# ptFlex.net
KiCad netlist of a schematic drawn in EAGLE
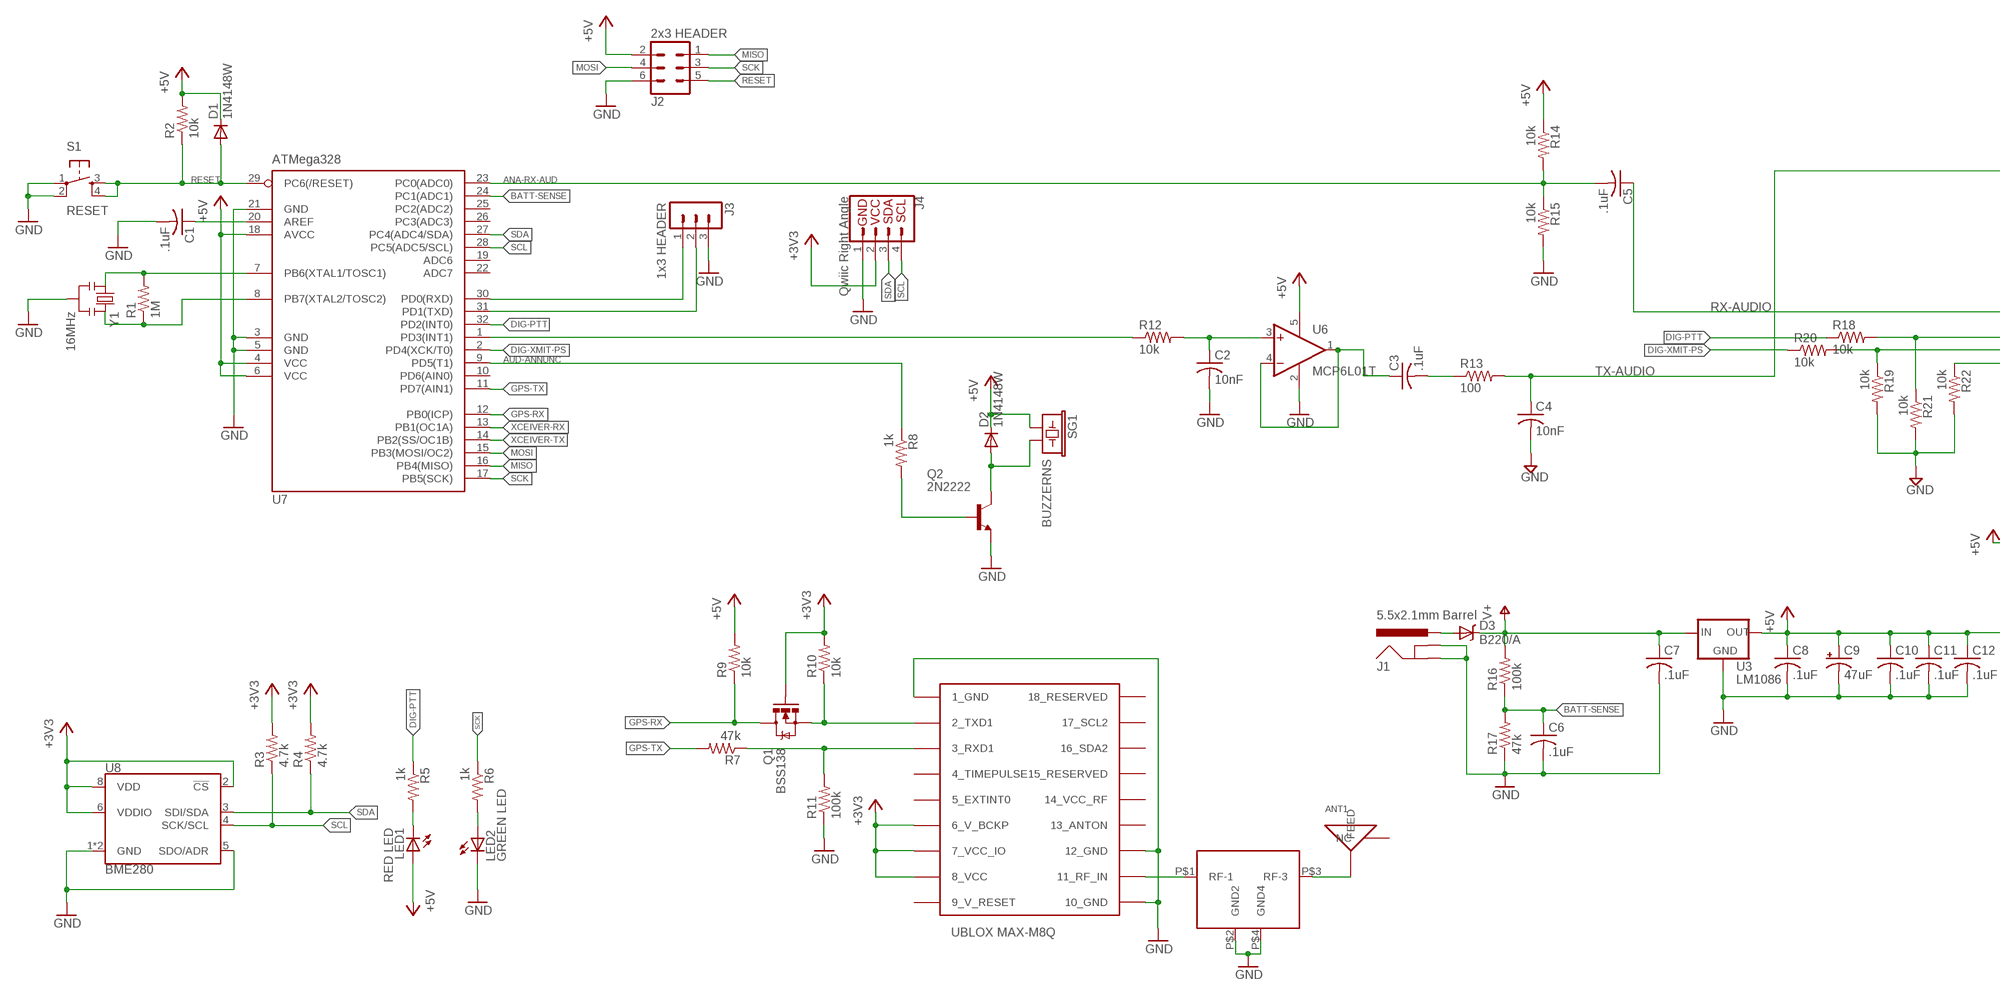
[diagram p0: schematic, sheet 1, part 1 of 2]
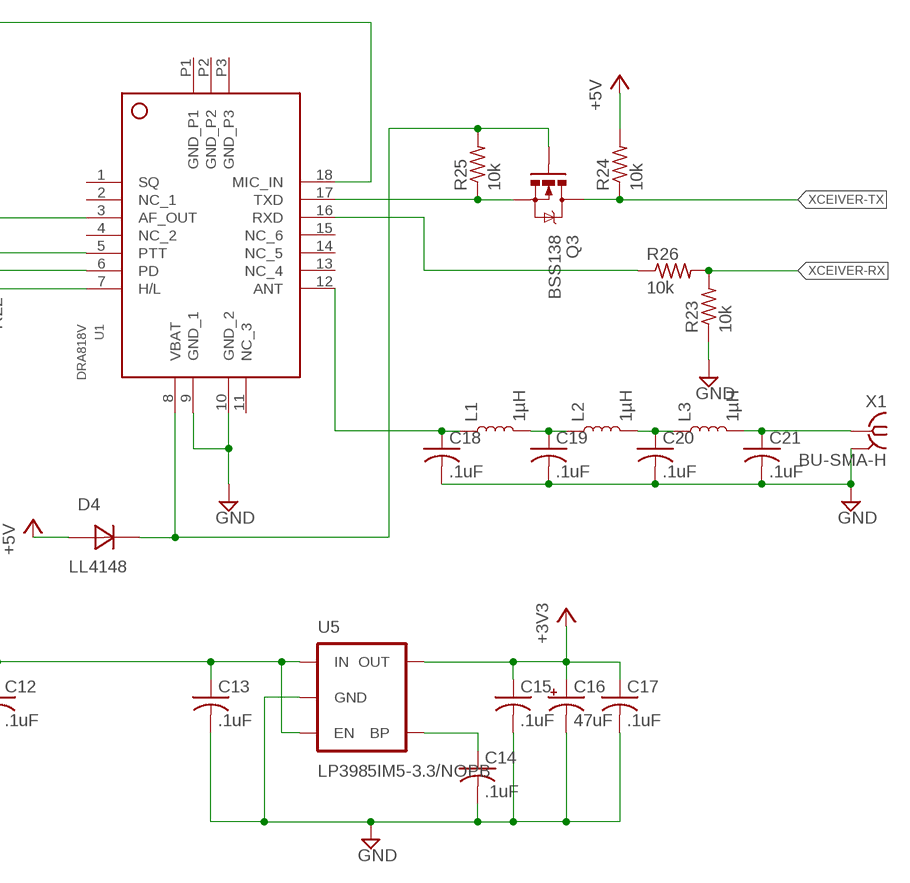
[diagram p1: schematic, sheet 1, part 2 of 2]

(export (version "E")
  (design (tool "Eeschema 10.0.6"))
  (components
    (comp (ref "ANT1")
      (value "GPS ANTENNA")
      (footprint "eagle-import:1575AT43A40")
      (libsource (lib "eagle-import") (part "GPS_ANT_SMDBAR"))
    )
    (comp (ref "C1")
      (value ".1uF")
      (footprint "eagle-import:C0805")
      (libsource (lib "eagle-import") (part "C-USC0805"))
    )
    (comp (ref "C2")
      (value "10nF")
      (footprint "eagle-import:C0805")
      (libsource (lib "eagle-import") (part "C-USC0805"))
    )
    (comp (ref "C3")
      (value ".1uF")
      (footprint "eagle-import:C0805")
      (libsource (lib "eagle-import") (part "C-USC0805"))
    )
    (comp (ref "C4")
      (value "10nF")
      (footprint "eagle-import:C0805")
      (libsource (lib "eagle-import") (part "C-USC0805"))
    )
    (comp (ref "C5")
      (value ".1uF")
      (footprint "eagle-import:C0805")
      (libsource (lib "eagle-import") (part "C-USC0805"))
    )
    (comp (ref "C6")
      (value ".1uF")
      (footprint "eagle-import:C0805")
      (libsource (lib "eagle-import") (part "C-USC0805"))
    )
    (comp (ref "C7")
      (value ".1uF")
      (footprint "eagle-import:C0805")
      (libsource (lib "eagle-import") (part "C-USC0805"))
    )
    (comp (ref "C8")
      (value ".1uF")
      (footprint "eagle-import:C0805")
      (libsource (lib "eagle-import") (part "C-USC0805"))
    )
    (comp (ref "C9")
      (value "47uF")
      (footprint "eagle-import:153CLV-0605")
      (libsource (lib "eagle-import") (part "CPOL-US153CLV-0605"))
    )
    (comp (ref "C10")
      (value ".1uF")
      (footprint "eagle-import:C0805")
      (libsource (lib "eagle-import") (part "C-USC0805"))
    )
    (comp (ref "C11")
      (value ".1uF")
      (footprint "eagle-import:C0805")
      (libsource (lib "eagle-import") (part "C-USC0805"))
    )
    (comp (ref "C12")
      (value ".1uF")
      (footprint "eagle-import:C0805")
      (libsource (lib "eagle-import") (part "C-USC0805"))
    )
    (comp (ref "C13")
      (value ".1uF")
      (footprint "eagle-import:C0805")
      (libsource (lib "eagle-import") (part "C-USC0805"))
    )
    (comp (ref "C14")
      (value ".1uF")
      (footprint "eagle-import:C0805")
      (libsource (lib "eagle-import") (part "C-USC0805"))
    )
    (comp (ref "C15")
      (value ".1uF")
      (footprint "eagle-import:C0805")
      (libsource (lib "eagle-import") (part "C-USC0805"))
    )
    (comp (ref "C16")
      (value "47uF")
      (footprint "eagle-import:153CLV-0605")
      (libsource (lib "eagle-import") (part "CPOL-US153CLV-0605"))
    )
    (comp (ref "C17")
      (value ".1uF")
      (footprint "eagle-import:C0805")
      (libsource (lib "eagle-import") (part "C-USC0805"))
    )
    (comp (ref "C18")
      (value ".1uF")
      (footprint "eagle-import:C0805")
      (libsource (lib "eagle-import") (part "C-USC0805"))
    )
    (comp (ref "C19")
      (value ".1uF")
      (footprint "eagle-import:C0805")
      (libsource (lib "eagle-import") (part "C-USC0805"))
    )
    (comp (ref "C20")
      (value ".1uF")
      (footprint "eagle-import:C0805")
      (libsource (lib "eagle-import") (part "C-USC0805"))
    )
    (comp (ref "C21")
      (value ".1uF")
      (footprint "eagle-import:C0805")
      (libsource (lib "eagle-import") (part "C-USC0805"))
    )
    (comp (ref "D1")
      (value "1N4148W")
      (footprint "eagle-import:SOD123")
      (libsource (lib "eagle-import") (part "DIODE-SOD123"))
    )
    (comp (ref "D2")
      (value "1N4148W")
      (footprint "eagle-import:SOD123")
      (libsource (lib "eagle-import") (part "DIODE-SOD123"))
    )
    (comp (ref "D3")
      (value "B220/A")
      (footprint "eagle-import:SMA-DIODE")
      (libsource (lib "eagle-import") (part "B340A"))
    )
    (comp (ref "D4")
      (value "LL4148")
      (footprint "eagle-import:SOD-80")
      (libsource (lib "eagle-import") (part "LL4148"))
    )
    (comp (ref "F1")
      (value "MURATA-GPS-FILTER")
      (footprint "eagle-import:MURATA-GPS-FILTER")
      (libsource (lib "eagle-import") (part "MURATA-GPS-FILTER"))
    )
    (comp (ref "J1")
      (value "5.5x2.1mm Barrel")
      (footprint "eagle-import:POWER_JACK_SMD")
      (libsource (lib "eagle-import") (part "POWER_JACKSMD"))
    )
    (comp (ref "J2")
      (value "2x3 HEADER")
      (footprint "eagle-import:MA03-2")
      (libsource (lib "eagle-import") (part "MA03-2"))
    )
    (comp (ref "J3")
      (value "1x3 HEADER")
      (footprint "eagle-import:MA03-1")
      (libsource (lib "eagle-import") (part "MA03-1"))
    )
    (comp (ref "J4")
      (value "Qwiic Right Angle")
      (footprint "eagle-import:1X04_1MM_RA")
      (libsource (lib "eagle-import") (part "I2C_STANDARDQWIIC"))
    )
    (comp (ref "L1")
      (value "1µH")
      (footprint "eagle-import:L0805")
      (libsource (lib "eagle-import") (part "INDUCTOR"))
    )
    (comp (ref "L2")
      (value "1µH")
      (footprint "eagle-import:L0805")
      (libsource (lib "eagle-import") (part "INDUCTOR"))
    )
    (comp (ref "L3")
      (value "1µH")
      (footprint "eagle-import:L0805")
      (libsource (lib "eagle-import") (part "INDUCTOR"))
    )
    (comp (ref "LED1")
      (value "RED LED")
      (footprint "eagle-import:CHIPLED_1206")
      (libsource (lib "eagle-import") (part "LEDCHIPLED_1206"))
    )
    (comp (ref "LED2")
      (value "GREEN LED")
      (footprint "eagle-import:CHIPLED_1206")
      (libsource (lib "eagle-import") (part "LEDCHIPLED_1206"))
    )
    (comp (ref "Q1")
      (value "BSS138")
      (footprint "eagle-import:SOT23")
      (libsource (lib "eagle-import") (part "MOSFET-NCHANNELBSS138"))
    )
    (comp (ref "Q2")
      (value "2N2222")
      (footprint "eagle-import:SOT23-BEC")
      (libsource (lib "eagle-import") (part "BC817SMD-16LT1"))
    )
    (comp (ref "Q3")
      (value "BSS138")
      (footprint "eagle-import:SOT23")
      (libsource (lib "eagle-import") (part "MOSFET-NCHANNELBSS138"))
    )
    (comp (ref "R1")
      (value "1M")
      (footprint "eagle-import:R0805")
      (libsource (lib "eagle-import") (part "R-US_R0805"))
    )
    (comp (ref "R2")
      (value "10k")
      (footprint "eagle-import:R0805")
      (libsource (lib "eagle-import") (part "R-US_R0805"))
    )
    (comp (ref "R3")
      (value "4.7k")
      (footprint "eagle-import:R0805")
      (libsource (lib "eagle-import") (part "R-US_R0805"))
    )
    (comp (ref "R4")
      (value "4.7k")
      (footprint "eagle-import:R0805")
      (libsource (lib "eagle-import") (part "R-US_R0805"))
    )
    (comp (ref "R5")
      (value "1k")
      (footprint "eagle-import:R0805")
      (libsource (lib "eagle-import") (part "R-US_R0805"))
    )
    (comp (ref "R6")
      (value "1k")
      (footprint "eagle-import:R0805")
      (libsource (lib "eagle-import") (part "R-US_R0805"))
    )
    (comp (ref "R7")
      (value "47k")
      (footprint "eagle-import:R0805")
      (libsource (lib "eagle-import") (part "R-US_R0805"))
    )
    (comp (ref "R8")
      (value "1k")
      (footprint "eagle-import:R0805")
      (libsource (lib "eagle-import") (part "R-US_R0805"))
    )
    (comp (ref "R9")
      (value "10k")
      (footprint "eagle-import:R0805")
      (libsource (lib "eagle-import") (part "R-US_R0805"))
    )
    (comp (ref "R10")
      (value "10k")
      (footprint "eagle-import:R0805")
      (libsource (lib "eagle-import") (part "R-US_R0805"))
    )
    (comp (ref "R11")
      (value "100k")
      (footprint "eagle-import:R0805")
      (libsource (lib "eagle-import") (part "R-US_R0805"))
    )
    (comp (ref "R12")
      (value "10k")
      (footprint "eagle-import:R0805")
      (libsource (lib "eagle-import") (part "R-US_R0805"))
    )
    (comp (ref "R13")
      (value "100")
      (footprint "eagle-import:R0805")
      (libsource (lib "eagle-import") (part "R-US_R0805"))
    )
    (comp (ref "R14")
      (value "10k")
      (footprint "eagle-import:R0805")
      (libsource (lib "eagle-import") (part "R-US_R0805"))
    )
    (comp (ref "R15")
      (value "10k")
      (footprint "eagle-import:R0805")
      (libsource (lib "eagle-import") (part "R-US_R0805"))
    )
    (comp (ref "R16")
      (value "100k")
      (footprint "eagle-import:R0805")
      (libsource (lib "eagle-import") (part "R-US_R0805"))
    )
    (comp (ref "R17")
      (value "47k")
      (footprint "eagle-import:R0805")
      (libsource (lib "eagle-import") (part "R-US_R0805"))
    )
    (comp (ref "R18")
      (value "10k")
      (footprint "eagle-import:R0805")
      (libsource (lib "eagle-import") (part "R-US_R0805"))
    )
    (comp (ref "R19")
      (value "10k")
      (footprint "eagle-import:R0805")
      (libsource (lib "eagle-import") (part "R-US_R0805"))
    )
    (comp (ref "R20")
      (value "10k")
      (footprint "eagle-import:R0805")
      (libsource (lib "eagle-import") (part "R-US_R0805"))
    )
    (comp (ref "R21")
      (value "10k")
      (footprint "eagle-import:R0805")
      (libsource (lib "eagle-import") (part "R-US_R0805"))
    )
    (comp (ref "R22")
      (value "10k")
      (footprint "eagle-import:R0805")
      (libsource (lib "eagle-import") (part "R-US_R0805"))
    )
    (comp (ref "R23")
      (value "10k")
      (footprint "eagle-import:R0805")
      (libsource (lib "eagle-import") (part "R-US_R0805"))
    )
    (comp (ref "R24")
      (value "10k")
      (footprint "eagle-import:R0805")
      (libsource (lib "eagle-import") (part "R-US_R0805"))
    )
    (comp (ref "R25")
      (value "10k")
      (footprint "eagle-import:R0805")
      (libsource (lib "eagle-import") (part "R-US_R0805"))
    )
    (comp (ref "R26")
      (value "10k")
      (footprint "eagle-import:R0805")
      (libsource (lib "eagle-import") (part "R-US_R0805"))
    )
    (comp (ref "S1")
      (value "RESET")
      (footprint "eagle-import:TACTILE_SWITCH_SMD")
      (libsource (lib "eagle-import") (part "TAC_SWITCHSMD"))
    )
    (comp (ref "SG1")
      (value "BUZZERNS")
      (footprint "eagle-import:BUZZER-12MM-NS")
      (libsource (lib "eagle-import") (part "BUZZERNS"))
    )
    (comp (ref "U1")
      (value "DRA818V")
      (footprint "eagle-import:SMD_DRA818")
      (libsource (lib "eagle-import") (part "DRA818V"))
    )
    (comp (ref "U2")
      (value "UBLOX_MAX")
      (footprint "eagle-import:UBLOX_MAX")
      (fields (field (name "ALT-PART") "UBLOX MAX-M8Q"))
      (libsource (lib "eagle-import") (part "UBLOX_MAX"))
    )
    (comp (ref "U3")
      (value "LM1086")
      (footprint "eagle-import:TO263")
      (libsource (lib "eagle-import") (part "LM1086TO263"))
    )
    (comp (ref "U5")
      (value "LP3985IM5-3.3/NOPB")
      (footprint "eagle-import:SOT23-5")
      (libsource (lib "eagle-import") (part "V_REG_LDOSMD"))
    )
    (comp (ref "U6")
      (value "MCP6L01T")
      (footprint "eagle-import:SOT23-5")
      (libsource (lib "eagle-import") (part "OPA725DBV"))
    )
    (comp (ref "U7")
      (value "ATMega328")
      (footprint "eagle-import:TQFP32-08")
      (fields (field (name "MPN") "ATMEGA8-16AU"))
      (libsource (lib "eagle-import") (part "MEGA8-AI"))
    )
    (comp (ref "U8")
      (value "BME280")
      (footprint "eagle-import:LGA-8-2.5X2.5")
      (libsource (lib "eagle-import") (part "BME280"))
    )
    (comp (ref "X1")
      (value "BU-SMA-H")
      (footprint "eagle-import:BU-SMA-H")
      (libsource (lib "eagle-import") (part "BU-SMA-H"))
    )
    (comp (ref "Y1")
      (value "16MHz")
      (footprint "eagle-import:RESONATOR-SMD")
      (libsource (lib "eagle-import") (part "RESONATOR16MHZ"))
    )
  )
  (nets
    (net (code "1") (name "+3V3") (class "Default")
      (node (ref "C15") (pin "1") (pinfunction "1_1") (pintype "passive"))
      (node (ref "C16") (pin "+") (pinfunction "+_+") (pintype "passive"))
      (node (ref "C17") (pin "1") (pinfunction "1_1") (pintype "passive"))
      (node (ref "J4") (pin "2") (pinfunction "2_2") (pintype "power_in"))
      (node (ref "Q1") (pin "1") (pinfunction "G_1") (pintype "passive"))
      (node (ref "R10") (pin "2") (pinfunction "2_2") (pintype "passive"))
      (node (ref "R3") (pin "2") (pinfunction "2_2") (pintype "passive"))
      (node (ref "R4") (pin "2") (pinfunction "2_2") (pintype "passive"))
      (node (ref "U2") (pin "6_V_BCKP") (pinfunction "6_V_BCKP_6_V_BCKP") (pintype "bidirectional"))
      (node (ref "U2") (pin "7_VCC_IO") (pinfunction "7_VCC_IO_7_VCC_IO") (pintype "power_in"))
      (node (ref "U2") (pin "8_VCC") (pinfunction "8_VCC_8_VCC") (pintype "power_in"))
      (node (ref "U5") (pin "5") (pinfunction "OUT_5") (pintype "passive"))
      (node (ref "U8") (pin "2") (pinfunction "~{CS}_2") (pintype "bidirectional"))
      (node (ref "U8") (pin "6") (pinfunction "VDDIO_6") (pintype "bidirectional"))
      (node (ref "U8") (pin "8") (pinfunction "VDD_8") (pintype "bidirectional"))
    )
    (net (code "2") (name "+5V") (class "Default")
      (node (ref "C10") (pin "1") (pinfunction "1_1") (pintype "passive"))
      (node (ref "C11") (pin "1") (pinfunction "1_1") (pintype "passive"))
      (node (ref "C12") (pin "1") (pinfunction "1_1") (pintype "passive"))
      (node (ref "C13") (pin "1") (pinfunction "1_1") (pintype "passive"))
      (node (ref "C8") (pin "1") (pinfunction "1_1") (pintype "passive"))
      (node (ref "C9") (pin "+") (pinfunction "+_+") (pintype "passive"))
      (node (ref "D1") (pin "C") (pinfunction "C_C") (pintype "passive"))
      (node (ref "D2") (pin "C") (pinfunction "C_C") (pintype "passive"))
      (node (ref "D4") (pin "ANODE") (pinfunction "ANODE_ANODE") (pintype "passive"))
      (node (ref "J2") (pin "2") (pinfunction "2_2") (pintype "passive"))
      (node (ref "LED1") (pin "A") (pinfunction "A_A") (pintype "passive"))
      (node (ref "R14") (pin "1") (pinfunction "1_1") (pintype "passive"))
      (node (ref "R2") (pin "2") (pinfunction "2_2") (pintype "passive"))
      (node (ref "R24") (pin "2") (pinfunction "2_2") (pintype "passive"))
      (node (ref "R9") (pin "2") (pinfunction "2_2") (pintype "passive"))
      (node (ref "SG1") (pin "+") (pinfunction "1_+") (pintype "passive"))
      (node (ref "U3") (pin "2") (pinfunction "OUT_2") (pintype "passive"))
      (node (ref "U5") (pin "1") (pinfunction "IN_1") (pintype "input"))
      (node (ref "U5") (pin "3") (pinfunction "EN_3") (pintype "input"))
      (node (ref "U6") (pin "5") (pinfunction "V+_5") (pintype "power_in"))
      (node (ref "U7") (pin "18") (pinfunction "AVCC_18") (pintype "power_in"))
      (node (ref "U7") (pin "4") (pinfunction "VCC_4") (pintype "power_in"))
      (node (ref "U7") (pin "6") (pinfunction "VCC_6") (pintype "power_in"))
    )
    (net (code "3") (name "/9_V_RESET") (class "Default")
      (node (ref "U2") (pin "9_V_RESET") (pinfunction "9_V_RESET_9_V_RESET") (pintype "power_in"))
    )
    (net (code "4") (name "/ANA-RX-AUD") (class "Default")
      (node (ref "C5") (pin "2") (pinfunction "2_2") (pintype "passive"))
      (node (ref "R14") (pin "2") (pinfunction "2_2") (pintype "passive"))
      (node (ref "R15") (pin "1") (pinfunction "1_1") (pintype "passive"))
      (node (ref "U7") (pin "23") (pinfunction "PC0(ADC0)_23") (pintype "bidirectional"))
    )
    (net (code "5") (name "/AUD-ANNUNC") (class "Default")
      (node (ref "R8") (pin "1") (pinfunction "1_1") (pintype "passive"))
      (node (ref "U7") (pin "9") (pinfunction "PD5(T1)_9") (pintype "bidirectional"))
    )
    (net (code "6") (name "/RX-AUDIO") (class "Default")
      (node (ref "C5") (pin "1") (pinfunction "1_1") (pintype "passive"))
      (node (ref "U1") (pin "3") (pinfunction "AF_OUT_3") (pintype "bidirectional"))
    )
    (net (code "7") (name "/TX-AUDIO") (class "Default")
      (node (ref "C3") (pin "2") (pinfunction "2_2") (pintype "passive"))
      (node (ref "R13") (pin "1") (pinfunction "1_1") (pintype "passive"))
    )
    (net (code "8") (name "BATT-SENSE") (class "Default")
      (node (ref "C6") (pin "1") (pinfunction "1_1") (pintype "passive"))
      (node (ref "R16") (pin "1") (pinfunction "1_1") (pintype "passive"))
      (node (ref "R17") (pin "2") (pinfunction "2_2") (pintype "passive"))
      (node (ref "U7") (pin "24") (pinfunction "PC1(ADC1)_24") (pintype "bidirectional"))
    )
    (net (code "9") (name "DIG-PTT") (class "Default")
      (node (ref "R18") (pin "1") (pinfunction "1_1") (pintype "passive"))
      (node (ref "R5") (pin "1") (pinfunction "1_1") (pintype "passive"))
      (node (ref "U7") (pin "32") (pinfunction "PD2(INT0)_32") (pintype "bidirectional"))
    )
    (net (code "10") (name "DIG-XMIT-PS") (class "Default")
      (node (ref "R20") (pin "1") (pinfunction "1_1") (pintype "passive"))
      (node (ref "U7") (pin "2") (pinfunction "PD4(XCK/T0)_2") (pintype "bidirectional"))
    )
    (net (code "11") (name "GND") (class "Default")
      (node (ref "C1") (pin "2") (pinfunction "2_2") (pintype "passive"))
      (node (ref "C10") (pin "2") (pinfunction "2_2") (pintype "passive"))
      (node (ref "C11") (pin "2") (pinfunction "2_2") (pintype "passive"))
      (node (ref "C12") (pin "2") (pinfunction "2_2") (pintype "passive"))
      (node (ref "C13") (pin "2") (pinfunction "2_2") (pintype "passive"))
      (node (ref "C14") (pin "2") (pinfunction "2_2") (pintype "passive"))
      (node (ref "C15") (pin "2") (pinfunction "2_2") (pintype "passive"))
      (node (ref "C16") (pin "-") (pinfunction "-_-") (pintype "passive"))
      (node (ref "C17") (pin "2") (pinfunction "2_2") (pintype "passive"))
      (node (ref "C18") (pin "2") (pinfunction "2_2") (pintype "passive"))
      (node (ref "C19") (pin "2") (pinfunction "2_2") (pintype "passive"))
      (node (ref "C2") (pin "2") (pinfunction "2_2") (pintype "passive"))
      (node (ref "C20") (pin "2") (pinfunction "2_2") (pintype "passive"))
      (node (ref "C21") (pin "2") (pinfunction "2_2") (pintype "passive"))
      (node (ref "C4") (pin "2") (pinfunction "2_2") (pintype "passive"))
      (node (ref "C6") (pin "2") (pinfunction "2_2") (pintype "passive"))
      (node (ref "C7") (pin "2") (pinfunction "2_2") (pintype "passive"))
      (node (ref "C8") (pin "2") (pinfunction "2_2") (pintype "passive"))
      (node (ref "C9") (pin "-") (pinfunction "-_-") (pintype "passive"))
      (node (ref "F1") (pin "P$2") (pinfunction "GND2_P$2") (pintype "power_in"))
      (node (ref "F1") (pin "P$4") (pinfunction "GND4_P$4") (pintype "power_in"))
      (node (ref "J1") (pin "GND") (pinfunction "GNDBREAK_GND") (pintype "bidirectional"))
      (node (ref "J1") (pin "P$4") (pinfunction "GND_P$4") (pintype "bidirectional"))
      (node (ref "J2") (pin "6") (pinfunction "6_6") (pintype "passive"))
      (node (ref "J3") (pin "3") (pinfunction "3_3") (pintype "passive"))
      (node (ref "J4") (pin "1") (pinfunction "1_1") (pintype "power_in"))
      (node (ref "LED2") (pin "C") (pinfunction "C_C") (pintype "passive"))
      (node (ref "Q2") (pin "E") (pinfunction "E_E") (pintype "passive"))
      (node (ref "R11") (pin "1") (pinfunction "1_1") (pintype "passive"))
      (node (ref "R15") (pin "2") (pinfunction "2_2") (pintype "passive"))
      (node (ref "R17") (pin "1") (pinfunction "1_1") (pintype "passive"))
      (node (ref "R19") (pin "2") (pinfunction "2_2") (pintype "passive"))
      (node (ref "R21") (pin "2") (pinfunction "2_2") (pintype "passive"))
      (node (ref "R22") (pin "2") (pinfunction "2_2") (pintype "passive"))
      (node (ref "R23") (pin "1") (pinfunction "1_1") (pintype "passive"))
      (node (ref "S1") (pin "1") (pinfunction "1_1") (pintype "passive"))
      (node (ref "S1") (pin "2") (pinfunction "2_2") (pintype "passive"))
      (node (ref "U1") (pin "10") (pinfunction "GND_2_10") (pintype "bidirectional"))
      (node (ref "U1") (pin "9") (pinfunction "GND_1_9") (pintype "bidirectional"))
      (node (ref "U2") (pin "10_GND") (pinfunction "10_GND_10_GND") (pintype "power_in"))
      (node (ref "U2") (pin "12_GND") (pinfunction "12_GND_12_GND") (pintype "power_in"))
      (node (ref "U2") (pin "1_GND") (pinfunction "1_GND_1_GND") (pintype "power_in"))
      (node (ref "U3") (pin "1") (pinfunction "GND_1") (pintype "input"))
      (node (ref "U5") (pin "2") (pinfunction "GND_2") (pintype "input"))
      (node (ref "U6") (pin "2") (pinfunction "V-_2") (pintype "power_in"))
      (node (ref "U7") (pin "21") (pinfunction "GND_21") (pintype "power_in"))
      (node (ref "U7") (pin "3") (pinfunction "GND_3") (pintype "power_in"))
      (node (ref "U7") (pin "5") (pinfunction "GND_5") (pintype "power_in"))
      (node (ref "U8") (pin "1") (pinfunction "GND_1") (pintype "bidirectional"))
      (node (ref "U8") (pin "5") (pinfunction "SDO/ADR_5") (pintype "bidirectional"))
      (node (ref "U8") (pin "7") (pinfunction "GND_7") (pintype "bidirectional"))
      (node (ref "X1") (pin "2") (pinfunction "2_2") (pintype "passive"))
      (node (ref "X1") (pin "3") (pinfunction "2_3") (pintype "passive"))
      (node (ref "X1") (pin "4") (pinfunction "2_4") (pintype "passive"))
      (node (ref "X1") (pin "5") (pinfunction "2_5") (pintype "passive"))
      (node (ref "Y1") (pin "2") (pinfunction "2_2") (pintype "passive"))
    )
    (net (code "12") (name "GPS-RX") (class "Default")
      (node (ref "Q1") (pin "3") (pinfunction "D_3") (pintype "passive"))
      (node (ref "R9") (pin "1") (pinfunction "1_1") (pintype "passive"))
      (node (ref "U7") (pin "12") (pinfunction "PB0(ICP)_12") (pintype "bidirectional"))
    )
    (net (code "13") (name "GPS-TX") (class "Default")
      (node (ref "R7") (pin "2") (pinfunction "2_2") (pintype "passive"))
      (node (ref "U7") (pin "11") (pinfunction "PD7(AIN1)_11") (pintype "bidirectional"))
    )
    (net (code "14") (name "MISO") (class "Default")
      (node (ref "J2") (pin "1") (pinfunction "1_1") (pintype "passive"))
      (node (ref "U7") (pin "16") (pinfunction "PB4(MISO)_16") (pintype "bidirectional"))
    )
    (net (code "15") (name "MOSI") (class "Default")
      (node (ref "J2") (pin "4") (pinfunction "4_4") (pintype "passive"))
      (node (ref "U7") (pin "15") (pinfunction "PB3(MOSI/OC2)_15") (pintype "bidirectional"))
    )
    (net (code "16") (name "Net-(C19-Pad1)") (class "Default")
      (node (ref "C19") (pin "1") (pinfunction "1_1") (pintype "passive"))
      (node (ref "L1") (pin "2") (pinfunction "2_2") (pintype "passive"))
      (node (ref "L2") (pin "1") (pinfunction "1_1") (pintype "passive"))
    )
    (net (code "17") (name "Net-(C20-Pad1)") (class "Default")
      (node (ref "C20") (pin "1") (pinfunction "1_1") (pintype "passive"))
      (node (ref "L2") (pin "2") (pinfunction "2_2") (pintype "passive"))
      (node (ref "L3") (pin "1") (pinfunction "1_1") (pintype "passive"))
    )
    (net (code "18") (name "Net-(C21-Pad1)") (class "Default")
      (node (ref "C21") (pin "1") (pinfunction "1_1") (pintype "passive"))
      (node (ref "L3") (pin "2") (pinfunction "2_2") (pintype "passive"))
      (node (ref "X1") (pin "1") (pinfunction "1_1") (pintype "passive"))
    )
    (net (code "19") (name "Net-(F1-RF-1)") (class "Default")
      (node (ref "F1") (pin "P$1") (pinfunction "RF-1_P$1") (pintype "bidirectional"))
      (node (ref "U2") (pin "11_RF_IN") (pinfunction "11_RF_IN_11_RF_IN") (pintype "bidirectional"))
    )
    (net (code "20") (name "Net-(F1-RF-3)") (class "Default")
      (node (ref "ANT1") (pin "FEED") (pinfunction "FEED_FEED") (pintype "bidirectional"))
      (node (ref "F1") (pin "P$3") (pinfunction "RF-3_P$3") (pintype "bidirectional"))
    )
    (net (code "21") (name "Net-(J1-PWR)") (class "Default")
      (node (ref "D3") (pin "A") (pinfunction "A_A") (pintype "passive"))
      (node (ref "J1") (pin "VIN0") (pinfunction "PWR_VIN0") (pintype "bidirectional"))
    )
    (net (code "22") (name "Net-(LED1-PadC)") (class "Default")
      (node (ref "LED1") (pin "C") (pinfunction "C_C") (pintype "passive"))
      (node (ref "R5") (pin "2") (pinfunction "2_2") (pintype "passive"))
    )
    (net (code "23") (name "Net-(LED2-PadA)") (class "Default")
      (node (ref "LED2") (pin "A") (pinfunction "A_A") (pintype "passive"))
      (node (ref "R6") (pin "2") (pinfunction "2_2") (pintype "passive"))
    )
    (net (code "24") (name "Net-(Q1-S)") (class "Default")
      (node (ref "Q1") (pin "2") (pinfunction "S_2") (pintype "passive"))
      (node (ref "R10") (pin "1") (pinfunction "1_1") (pintype "passive"))
      (node (ref "U2") (pin "2_TXD1") (pinfunction "2_TXD1_2_TXD1") (pintype "bidirectional"))
    )
    (net (code "25") (name "Net-(Q2-PadB)") (class "Default")
      (node (ref "Q2") (pin "B") (pinfunction "B_B") (pintype "passive"))
      (node (ref "R8") (pin "2") (pinfunction "2_2") (pintype "passive"))
    )
    (net (code "26") (name "Net-(Q3-G)") (class "Default")
      (node (ref "D4") (pin "CATHODE") (pinfunction "CATHODE_CATHODE") (pintype "passive"))
      (node (ref "Q3") (pin "1") (pinfunction "G_1") (pintype "passive"))
      (node (ref "R25") (pin "2") (pinfunction "2_2") (pintype "passive"))
      (node (ref "U1") (pin "8") (pinfunction "VBAT_8") (pintype "bidirectional"))
    )
    (net (code "27") (name "Net-(Q3-S)") (class "Default")
      (node (ref "Q3") (pin "2") (pinfunction "S_2") (pintype "passive"))
      (node (ref "R25") (pin "1") (pinfunction "1_1") (pintype "passive"))
      (node (ref "U1") (pin "17") (pinfunction "TXD_17") (pintype "bidirectional"))
    )
    (net (code "28") (name "Net-(R11-Pad2)") (class "Default")
      (node (ref "R11") (pin "2") (pinfunction "2_2") (pintype "passive"))
      (node (ref "R7") (pin "1") (pinfunction "1_1") (pintype "passive"))
      (node (ref "U2") (pin "3_RXD1") (pinfunction "3_RXD1_3_RXD1") (pintype "bidirectional"))
    )
    (net (code "29") (name "Net-(SG1-2)") (class "Default")
      (node (ref "D2") (pin "A") (pinfunction "A_A") (pintype "passive"))
      (node (ref "Q2") (pin "C") (pinfunction "C_C") (pintype "passive"))
      (node (ref "SG1") (pin "-") (pinfunction "2_-") (pintype "passive"))
    )
    (net (code "30") (name "Net-(U1-ANT)") (class "Default")
      (node (ref "C18") (pin "1") (pinfunction "1_1") (pintype "passive"))
      (node (ref "L1") (pin "1") (pinfunction "1_1") (pintype "passive"))
      (node (ref "U1") (pin "12") (pinfunction "ANT_12") (pintype "bidirectional"))
    )
    (net (code "31") (name "Net-(U1-H{slash}L)") (class "Default")
      (node (ref "R22") (pin "1") (pinfunction "1_1") (pintype "passive"))
      (node (ref "U1") (pin "7") (pinfunction "H/L_7") (pintype "bidirectional"))
    )
    (net (code "32") (name "Net-(U1-MIC_IN)") (class "Default")
      (node (ref "C4") (pin "1") (pinfunction "1_1") (pintype "passive"))
      (node (ref "R13") (pin "2") (pinfunction "2_2") (pintype "passive"))
      (node (ref "U1") (pin "18") (pinfunction "MIC_IN_18") (pintype "bidirectional"))
    )
    (net (code "33") (name "Net-(U1-PD)") (class "Default")
      (node (ref "R19") (pin "1") (pinfunction "1_1") (pintype "passive"))
      (node (ref "R20") (pin "2") (pinfunction "2_2") (pintype "passive"))
      (node (ref "U1") (pin "6") (pinfunction "PD_6") (pintype "bidirectional"))
    )
    (net (code "34") (name "Net-(U1-PTT)") (class "Default")
      (node (ref "R18") (pin "2") (pinfunction "2_2") (pintype "passive"))
      (node (ref "R21") (pin "1") (pinfunction "1_1") (pintype "passive"))
      (node (ref "U1") (pin "5") (pinfunction "PTT_5") (pintype "bidirectional"))
    )
    (net (code "35") (name "Net-(U1-RXD)") (class "Default")
      (node (ref "R26") (pin "1") (pinfunction "1_1") (pintype "passive"))
      (node (ref "U1") (pin "16") (pinfunction "RXD_16") (pintype "bidirectional"))
    )
    (net (code "36") (name "Net-(U5-BP)") (class "Default")
      (node (ref "C14") (pin "1") (pinfunction "1_1") (pintype "passive"))
      (node (ref "U5") (pin "4") (pinfunction "BP_4") (pintype "input"))
    )
    (net (code "37") (name "Net-(U6-+IN)") (class "Default")
      (node (ref "C2") (pin "1") (pinfunction "1_1") (pintype "passive"))
      (node (ref "R12") (pin "2") (pinfunction "2_2") (pintype "passive"))
      (node (ref "U6") (pin "3") (pinfunction "+IN_3") (pintype "input"))
    )
    (net (code "38") (name "Net-(U6--IN)") (class "Default")
      (node (ref "C3") (pin "1") (pinfunction "1_1") (pintype "passive"))
      (node (ref "U6") (pin "1") (pinfunction "OUT_1") (pintype "output"))
      (node (ref "U6") (pin "4") (pinfunction "-IN_4") (pintype "input"))
    )
    (net (code "39") (name "Net-(U7-AREF)") (class "Default")
      (node (ref "C1") (pin "1") (pinfunction "1_1") (pintype "passive"))
      (node (ref "U7") (pin "20") (pinfunction "AREF_20") (pintype "passive"))
    )
    (net (code "40") (name "Net-(U7-PB6(XTAL1{slash}TOSC1))") (class "Default")
      (node (ref "R1") (pin "2") (pinfunction "2_2") (pintype "passive"))
      (node (ref "U7") (pin "7") (pinfunction "PB6(XTAL1/TOSC1)_7") (pintype "bidirectional"))
      (node (ref "Y1") (pin "1") (pinfunction "1_1") (pintype "passive"))
    )
    (net (code "41") (name "Net-(U7-PB7(XTAL2{slash}TOSC2))") (class "Default")
      (node (ref "R1") (pin "1") (pinfunction "1_1") (pintype "passive"))
      (node (ref "U7") (pin "8") (pinfunction "PB7(XTAL2/TOSC2)_8") (pintype "bidirectional"))
      (node (ref "Y1") (pin "3") (pinfunction "3_3") (pintype "passive"))
    )
    (net (code "42") (name "Net-(U7-PD0(RXD))") (class "Default")
      (node (ref "J3") (pin "1") (pinfunction "1_1") (pintype "passive"))
      (node (ref "U7") (pin "30") (pinfunction "PD0(RXD)_30") (pintype "bidirectional"))
    )
    (net (code "43") (name "Net-(U7-PD1(TXD))") (class "Default")
      (node (ref "J3") (pin "2") (pinfunction "2_2") (pintype "passive"))
      (node (ref "U7") (pin "31") (pinfunction "PD1(TXD)_31") (pintype "bidirectional"))
    )
    (net (code "44") (name "Net-(U7-PD3(INT1))") (class "Default")
      (node (ref "R12") (pin "1") (pinfunction "1_1") (pintype "passive"))
      (node (ref "U7") (pin "1") (pinfunction "PD3(INT1)_1") (pintype "bidirectional"))
    )
    (net (code "45") (name "RESET") (class "Default")
      (node (ref "D1") (pin "A") (pinfunction "A_A") (pintype "passive"))
      (node (ref "J2") (pin "5") (pinfunction "5_5") (pintype "passive"))
      (node (ref "R2") (pin "1") (pinfunction "1_1") (pintype "passive"))
      (node (ref "S1") (pin "3") (pinfunction "3_3") (pintype "passive"))
      (node (ref "S1") (pin "4") (pinfunction "4_4") (pintype "passive"))
      (node (ref "U7") (pin "29") (pinfunction "PC6(/RESET)_29") (pintype "bidirectional"))
    )
    (net (code "46") (name "SCK") (class "Default")
      (node (ref "J2") (pin "3") (pinfunction "3_3") (pintype "passive"))
      (node (ref "R6") (pin "1") (pinfunction "1_1") (pintype "passive"))
      (node (ref "U7") (pin "17") (pinfunction "PB5(SCK)_17") (pintype "bidirectional"))
    )
    (net (code "47") (name "SCL") (class "Default")
      (node (ref "J4") (pin "4") (pinfunction "4_4") (pintype "passive"))
      (node (ref "R3") (pin "1") (pinfunction "1_1") (pintype "passive"))
      (node (ref "U7") (pin "28") (pinfunction "PC5(ADC5/SCL)_28") (pintype "bidirectional"))
      (node (ref "U8") (pin "4") (pinfunction "SCK/SCL_4") (pintype "bidirectional"))
    )
    (net (code "48") (name "SDA") (class "Default")
      (node (ref "J4") (pin "3") (pinfunction "3_3") (pintype "passive"))
      (node (ref "R4") (pin "1") (pinfunction "1_1") (pintype "passive"))
      (node (ref "U7") (pin "27") (pinfunction "PC4(ADC4/SDA)_27") (pintype "bidirectional"))
      (node (ref "U8") (pin "3") (pinfunction "SDI/SDA_3") (pintype "bidirectional"))
    )
    (net (code "49") (name "V+") (class "Default")
      (node (ref "C7") (pin "1") (pinfunction "1_1") (pintype "passive"))
      (node (ref "D3") (pin "C") (pinfunction "C_C") (pintype "passive"))
      (node (ref "R16") (pin "2") (pinfunction "2_2") (pintype "passive"))
      (node (ref "U3") (pin "3") (pinfunction "IN_3") (pintype "input"))
    )
    (net (code "50") (name "XCEIVER-RX") (class "Default")
      (node (ref "R23") (pin "2") (pinfunction "2_2") (pintype "passive"))
      (node (ref "R26") (pin "2") (pinfunction "2_2") (pintype "passive"))
      (node (ref "U7") (pin "13") (pinfunction "PB1(OC1A)_13") (pintype "bidirectional"))
    )
    (net (code "51") (name "XCEIVER-TX") (class "Default")
      (node (ref "Q3") (pin "3") (pinfunction "D_3") (pintype "passive"))
      (node (ref "R24") (pin "1") (pinfunction "1_1") (pintype "passive"))
      (node (ref "U7") (pin "14") (pinfunction "PB2(SS/OC1B)_14") (pintype "bidirectional"))
    )
    (net (code "52") (name "unconnected-(ANT1-PadNC)") (class "Default")
      (node (ref "ANT1") (pin "NC") (pinfunction "NC_NC") (pintype "bidirectional"))
    )
    (net (code "53") (name "unconnected-(U1-GND_P1-PadP1)") (class "Default")
      (node (ref "U1") (pin "P1") (pinfunction "GND_P1_P1") (pintype "bidirectional"))
    )
    (net (code "54") (name "unconnected-(U1-GND_P2-PadP2)") (class "Default")
      (node (ref "U1") (pin "P2") (pinfunction "GND_P2_P2") (pintype "bidirectional"))
    )
    (net (code "55") (name "unconnected-(U1-GND_P3-PadP3)") (class "Default")
      (node (ref "U1") (pin "P3") (pinfunction "GND_P3_P3") (pintype "bidirectional"))
    )
    (net (code "56") (name "unconnected-(U1-NC_1-Pad2)") (class "Default")
      (node (ref "U1") (pin "2") (pinfunction "NC_1_2") (pintype "bidirectional"))
    )
    (net (code "57") (name "unconnected-(U1-NC_2-Pad4)") (class "Default")
      (node (ref "U1") (pin "4") (pinfunction "NC_2_4") (pintype "bidirectional"))
    )
    (net (code "58") (name "unconnected-(U1-NC_3-Pad11)") (class "Default")
      (node (ref "U1") (pin "11") (pinfunction "NC_3_11") (pintype "bidirectional"))
    )
    (net (code "59") (name "unconnected-(U1-NC_4-Pad13)") (class "Default")
      (node (ref "U1") (pin "13") (pinfunction "NC_4_13") (pintype "bidirectional"))
    )
    (net (code "60") (name "unconnected-(U1-NC_5-Pad14)") (class "Default")
      (node (ref "U1") (pin "14") (pinfunction "NC_5_14") (pintype "bidirectional"))
    )
    (net (code "61") (name "unconnected-(U1-NC_6-Pad15)") (class "Default")
      (node (ref "U1") (pin "15") (pinfunction "NC_6_15") (pintype "bidirectional"))
    )
    (net (code "62") (name "unconnected-(U1-SQ-Pad1)") (class "Default")
      (node (ref "U1") (pin "1") (pinfunction "SQ_1") (pintype "bidirectional"))
    )
    (net (code "63") (name "unconnected-(U2-Pad4_TIMEPULSE)") (class "Default")
      (node (ref "U2") (pin "4_TIMEPULSE") (pinfunction "4_TIMEPULSE_4_TIMEPULSE") (pintype "bidirectional"))
    )
    (net (code "64") (name "unconnected-(U2-Pad5_EXTINT0)") (class "Default")
      (node (ref "U2") (pin "5_EXTINT0") (pinfunction "5_EXTINT0_5_EXTINT0") (pintype "bidirectional"))
    )
    (net (code "65") (name "unconnected-(U2-Pad13_ANTON)") (class "Default")
      (node (ref "U2") (pin "13_ANTON") (pinfunction "13_ANTON_13_ANTON") (pintype "bidirectional"))
    )
    (net (code "66") (name "unconnected-(U2-Pad14_VCC_RF)") (class "Default")
      (node (ref "U2") (pin "14_VCC_RF") (pinfunction "14_VCC_RF_14_VCC_RF") (pintype "bidirectional"))
    )
    (net (code "67") (name "unconnected-(U2-Pad15_RESERVED)") (class "Default")
      (node (ref "U2") (pin "15_RESERVED") (pinfunction "15_RESERVED_15_RESERVED") (pintype "bidirectional"))
    )
    (net (code "68") (name "unconnected-(U2-Pad16_SDA2)") (class "Default")
      (node (ref "U2") (pin "16_SDA2") (pinfunction "16_SDA2_16_SDA2") (pintype "bidirectional"))
    )
    (net (code "69") (name "unconnected-(U2-Pad17_SCL2)") (class "Default")
      (node (ref "U2") (pin "17_SCL2") (pinfunction "17_SCL2_17_SCL2") (pintype "bidirectional"))
    )
    (net (code "70") (name "unconnected-(U2-Pad18_RESERVED)") (class "Default")
      (node (ref "U2") (pin "18_RESERVED") (pinfunction "18_RESERVED_18_RESERVED") (pintype "bidirectional"))
    )
    (net (code "71") (name "unconnected-(U7-ADC6-Pad19)") (class "Default")
      (node (ref "U7") (pin "19") (pinfunction "ADC6_19") (pintype "bidirectional"))
    )
    (net (code "72") (name "unconnected-(U7-ADC7-Pad22)") (class "Default")
      (node (ref "U7") (pin "22") (pinfunction "ADC7_22") (pintype "bidirectional"))
    )
    (net (code "73") (name "unconnected-(U7-PC2(ADC2)-Pad25)") (class "Default")
      (node (ref "U7") (pin "25") (pinfunction "PC2(ADC2)_25") (pintype "bidirectional"))
    )
    (net (code "74") (name "unconnected-(U7-PC3(ADC3)-Pad26)") (class "Default")
      (node (ref "U7") (pin "26") (pinfunction "PC3(ADC3)_26") (pintype "bidirectional"))
    )
    (net (code "75") (name "unconnected-(U7-PD6(AIN0)-Pad10)") (class "Default")
      (node (ref "U7") (pin "10") (pinfunction "PD6(AIN0)_10") (pintype "bidirectional"))
    )
  )
)
